# MultiWiiChassis_quadmini_power.net
KiCad netlist of a schematic drawn in EAGLE
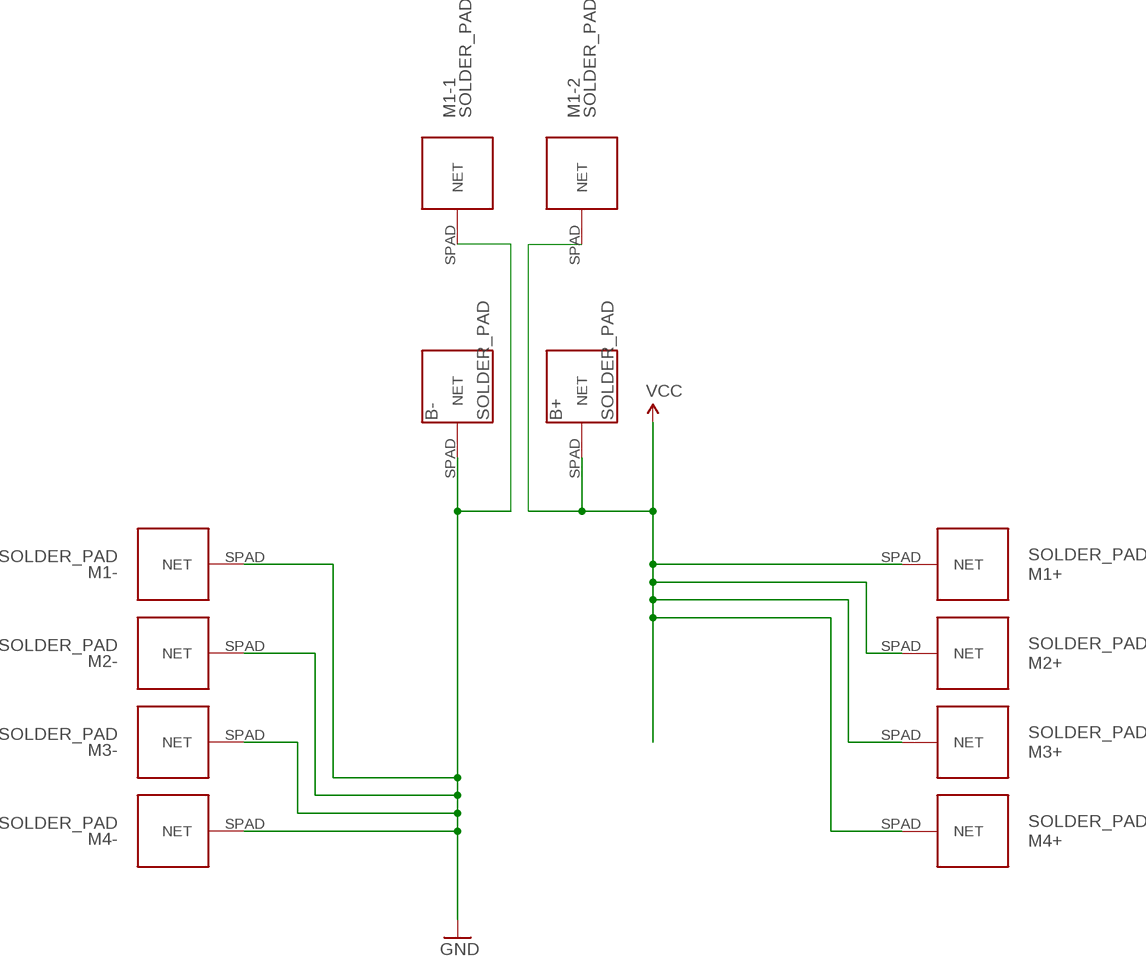
[diagram p0: schematic, sheet 1]

(export (version "E")
  (design (tool "Eeschema 10.0.6"))
  (components
    (comp (ref "B+")
      (value "SOLDER_PAD")
      (footprint "eagle-import:SOLDER_PAD")
      (libsource (lib "eagle-import") (part "SOLDER_PAD"))
    )
    (comp (ref "B-")
      (value "SOLDER_PAD")
      (footprint "eagle-import:SOLDER_PAD")
      (libsource (lib "eagle-import") (part "SOLDER_PAD"))
    )
    (comp (ref "M1+")
      (value "SOLDER_PAD")
      (footprint "eagle-import:SOLDER_PAD")
      (libsource (lib "eagle-import") (part "SOLDER_PAD"))
    )
    (comp (ref "M1-")
      (value "SOLDER_PAD")
      (footprint "eagle-import:SOLDER_PAD")
      (libsource (lib "eagle-import") (part "SOLDER_PAD"))
    )
    (comp (ref "M1-1")
      (value "SOLDER_PAD")
      (footprint "eagle-import:SOLDER_PAD")
      (libsource (lib "eagle-import") (part "SOLDER_PAD"))
    )
    (comp (ref "M1-2")
      (value "SOLDER_PAD")
      (footprint "eagle-import:SOLDER_PAD")
      (libsource (lib "eagle-import") (part "SOLDER_PAD"))
    )
    (comp (ref "M2+")
      (value "SOLDER_PAD")
      (footprint "eagle-import:SOLDER_PAD")
      (libsource (lib "eagle-import") (part "SOLDER_PAD"))
    )
    (comp (ref "M2-")
      (value "SOLDER_PAD")
      (footprint "eagle-import:SOLDER_PAD")
      (libsource (lib "eagle-import") (part "SOLDER_PAD"))
    )
    (comp (ref "M3+")
      (value "SOLDER_PAD")
      (footprint "eagle-import:SOLDER_PAD")
      (libsource (lib "eagle-import") (part "SOLDER_PAD"))
    )
    (comp (ref "M3-")
      (value "SOLDER_PAD")
      (footprint "eagle-import:SOLDER_PAD")
      (libsource (lib "eagle-import") (part "SOLDER_PAD"))
    )
    (comp (ref "M4+")
      (value "SOLDER_PAD")
      (footprint "eagle-import:SOLDER_PAD")
      (libsource (lib "eagle-import") (part "SOLDER_PAD"))
    )
    (comp (ref "M4-")
      (value "SOLDER_PAD")
      (footprint "eagle-import:SOLDER_PAD")
      (libsource (lib "eagle-import") (part "SOLDER_PAD"))
    )
  )
  (nets
    (net (code "1") (name "GND") (class "Default")
      (node (ref "B-") (pin "SPAD") (pinfunction "NET_SPAD") (pintype "bidirectional"))
      (node (ref "M1-") (pin "SPAD") (pinfunction "NET_SPAD") (pintype "bidirectional"))
      (node (ref "M1-1") (pin "SPAD") (pinfunction "NET_SPAD") (pintype "bidirectional"))
      (node (ref "M2-") (pin "SPAD") (pinfunction "NET_SPAD") (pintype "bidirectional"))
      (node (ref "M3-") (pin "SPAD") (pinfunction "NET_SPAD") (pintype "bidirectional"))
      (node (ref "M4-") (pin "SPAD") (pinfunction "NET_SPAD") (pintype "bidirectional"))
    )
    (net (code "2") (name "VCC") (class "Default")
      (node (ref "B+") (pin "SPAD") (pinfunction "NET_SPAD") (pintype "bidirectional"))
      (node (ref "M1+") (pin "SPAD") (pinfunction "NET_SPAD") (pintype "bidirectional"))
      (node (ref "M1-2") (pin "SPAD") (pinfunction "NET_SPAD") (pintype "bidirectional"))
      (node (ref "M2+") (pin "SPAD") (pinfunction "NET_SPAD") (pintype "bidirectional"))
      (node (ref "M3+") (pin "SPAD") (pinfunction "NET_SPAD") (pintype "bidirectional"))
      (node (ref "M4+") (pin "SPAD") (pinfunction "NET_SPAD") (pintype "bidirectional"))
    )
  )
)
